# mikrokontroler.net
KiCad netlist of a schematic drawn in Altium Designer
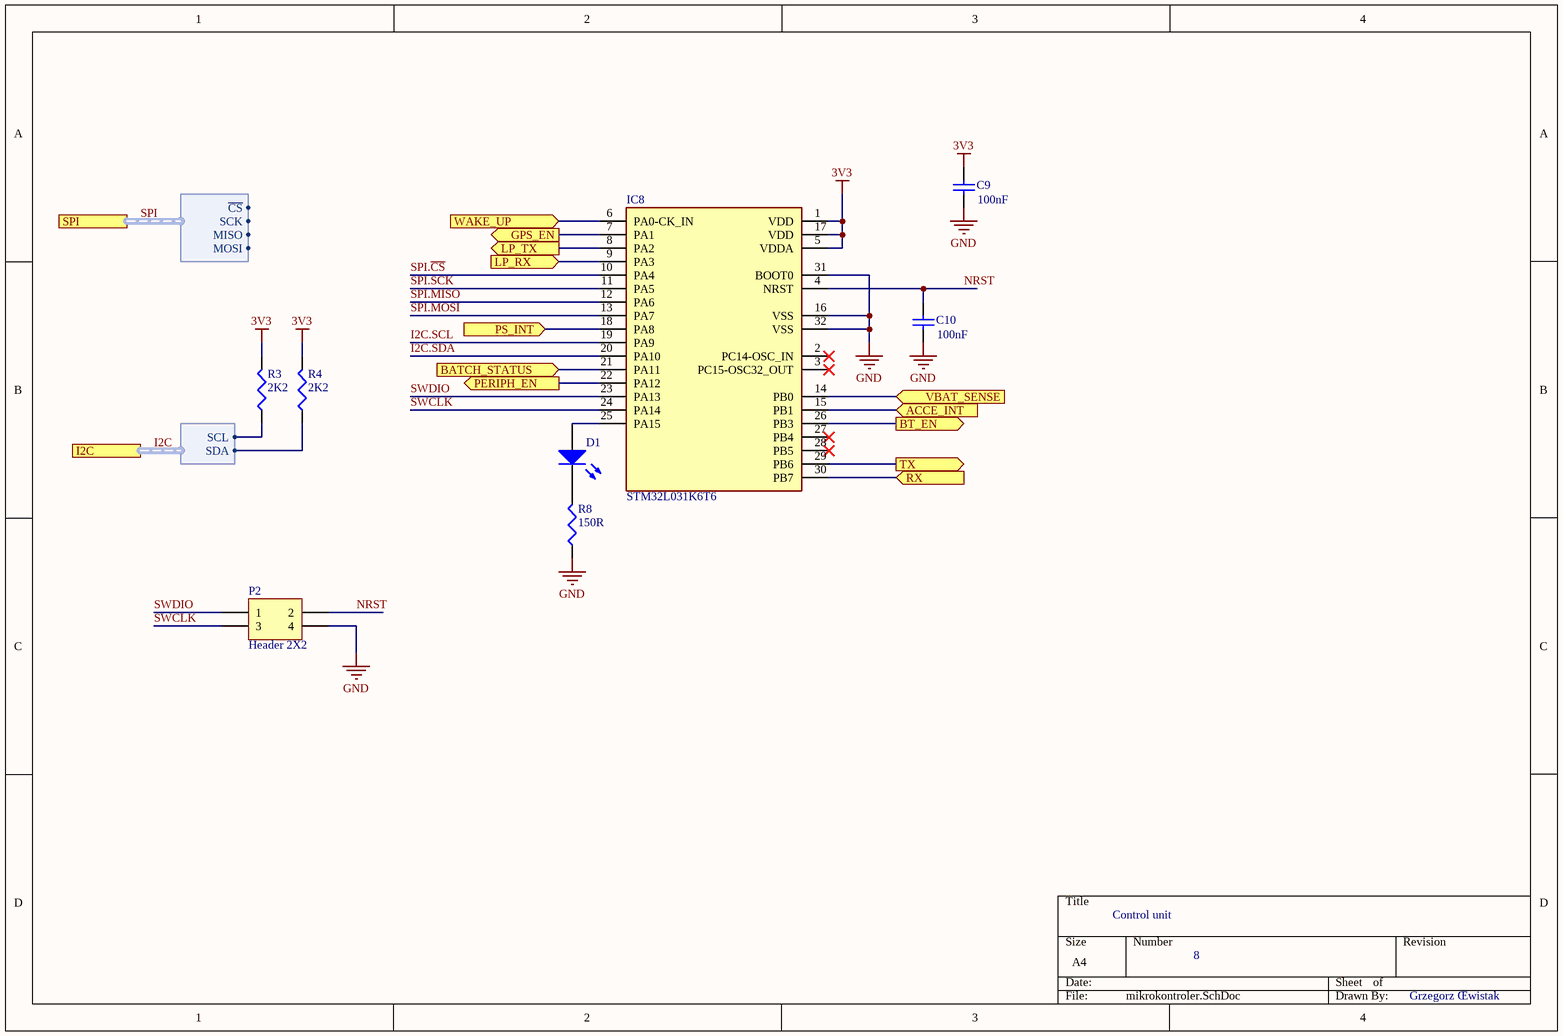
[diagram p0: mikrokontroler.SchDoc]

(export (version "E")
  (design (tool "Eeschema 10.0.6"))
  (components
    (comp (ref "C9")
      (value "100nF")
      (footprint "C0805")
      (description "Capacitor")
      (fields (field (name "Comment") "Cap") (field (name "PUBLISHER") "Altium Limited"))
      (libsource (lib "Miscellaneous Devices") (part "Cap"))
    )
    (comp (ref "C10")
      (value "100nF")
      (footprint "C0805")
      (description "Capacitor")
      (fields (field (name "Comment") "Cap") (field (name "PUBLISHER") "Altium Limited"))
      (libsource (lib "Miscellaneous Devices") (part "Cap"))
    )
    (comp (ref "D1")
      (value "LL-S192PUAC-2A")
      (footprint "LED_0603")
      (description "Typical BLUE SiC LED")
      (fields (field (name "PUBLISHER") "Altium Limited"))
      (libsource (lib "Miscellaneous Devices") (part "LED3"))
    )
    (comp (ref "IC8")
      (value "STM32L031K6T6")
      (footprint "QFP80P900X900X160-32N")
      (description "Integrated Circuit")
      (fields (field (name "MOUSER PART NUMBER") "511-STM32L031K6T6"))
      (libsource (lib "lib") (part "STM32L031K6T6"))
    )
    (comp (ref "P2")
      (value "Header 2X2")
      (footprint "2x2_header")
      (description "Header, 2-Pin, Dual row")
      (fields (field (name "PUBLISHER") "Altium Limited"))
      (libsource (lib "Miscellaneous Connectors") (part "Header 2X2"))
    )
    (comp (ref "R3")
      (value "2K2")
      (footprint "R0603")
      (description "Resistor")
      (fields (field (name "Comment") "Res3") (field (name "PUBLISHER") "Altium Limited"))
      (libsource (lib "Miscellaneous Devices") (part "Res3"))
    )
    (comp (ref "R4")
      (value "2K2")
      (footprint "R0603")
      (description "Resistor")
      (fields (field (name "Comment") "Res3") (field (name "PUBLISHER") "Altium Limited"))
      (libsource (lib "Miscellaneous Devices") (part "Res3"))
    )
    (comp (ref "R8")
      (value "150R")
      (footprint "R0603")
      (description "Resistor")
      (fields (field (name "Comment") "Res3") (field (name "PUBLISHER") "Altium Limited"))
      (libsource (lib "Miscellaneous Devices") (part "Res3"))
    )
  )
  (nets
    (net (code "3") (name "/ACCE_INT") (class "Default")
      (node (ref "IC8") (pin "15") (pinfunction "PB1_15") (pintype "passive"))
    )
    (net (code "4") (name "/BATCH_STATUS") (class "Default")
      (node (ref "IC8") (pin "21") (pinfunction "PA11_21") (pintype "passive"))
    )
    (net (code "5") (name "/BT_EN") (class "Default")
      (node (ref "IC8") (pin "26") (pinfunction "PB3_26") (pintype "passive"))
    )
    (net (code "6") (name "/GPS_EN") (class "Default")
      (node (ref "IC8") (pin "7") (pinfunction "PA1_7") (pintype "passive"))
    )
    (net (code "7") (name "/I2C.SCL") (class "Default")
      (node (ref "IC8") (pin "19") (pinfunction "PA9_19") (pintype "passive"))
    )
    (net (code "8") (name "/I2C.SDA") (class "Default")
      (node (ref "IC8") (pin "20") (pinfunction "PA10_20") (pintype "passive"))
    )
    (net (code "10") (name "/LP_RX") (class "Default")
      (node (ref "IC8") (pin "9") (pinfunction "PA3_9") (pintype "passive"))
    )
    (net (code "11") (name "/LP_TX") (class "Default")
      (node (ref "IC8") (pin "8") (pinfunction "PA2_8") (pintype "passive"))
    )
    (net (code "12") (name "/NRST") (class "Default")
      (node (ref "C10") (pin "2") (pinfunction "2_2") (pintype "passive"))
      (node (ref "IC8") (pin "4") (pinfunction "NRST_4") (pintype "passive"))
      (node (ref "P2") (pin "2") (pinfunction "2_2") (pintype "passive"))
    )
    (net (code "13") (name "/PERIPH_EN") (class "Default")
      (node (ref "IC8") (pin "22") (pinfunction "PA12_22") (pintype "passive"))
    )
    (net (code "14") (name "/PS_INT") (class "Default")
      (node (ref "IC8") (pin "18") (pinfunction "PA8_18") (pintype "passive"))
    )
    (net (code "15") (name "/RX") (class "Default")
      (node (ref "IC8") (pin "30") (pinfunction "PB7_30") (pintype "passive"))
    )
    (net (code "16") (name "/SCL") (class "Default")
      (node (ref "R3") (pin "1") (pinfunction "1_1") (pintype "passive"))
    )
    (net (code "17") (name "/SDA") (class "Default")
      (node (ref "R4") (pin "1") (pinfunction "1_1") (pintype "passive"))
    )
    (net (code "18") (name "/SPI.MISO") (class "Default")
      (node (ref "IC8") (pin "12") (pinfunction "PA6_12") (pintype "passive"))
    )
    (net (code "19") (name "/SPI.MOSI") (class "Default")
      (node (ref "IC8") (pin "13") (pinfunction "PA7_13") (pintype "passive"))
    )
    (net (code "20") (name "/SPI.SCK") (class "Default")
      (node (ref "IC8") (pin "11") (pinfunction "PA5_11") (pintype "passive"))
    )
    (net (code "21") (name "/SPI.~{CS}") (class "Default")
      (node (ref "IC8") (pin "10") (pinfunction "PA4_10") (pintype "passive"))
    )
    (net (code "23") (name "/SWCLK") (class "Default")
      (node (ref "IC8") (pin "24") (pinfunction "PA14_24") (pintype "passive"))
      (node (ref "P2") (pin "3") (pinfunction "3_3") (pintype "passive"))
    )
    (net (code "24") (name "/SWDIO") (class "Default")
      (node (ref "IC8") (pin "23") (pinfunction "PA13_23") (pintype "passive"))
      (node (ref "P2") (pin "1") (pinfunction "1_1") (pintype "passive"))
    )
    (net (code "25") (name "/TX") (class "Default")
      (node (ref "IC8") (pin "29") (pinfunction "PB6_29") (pintype "passive"))
    )
    (net (code "26") (name "/VBAT_SENSE") (class "Default")
      (node (ref "IC8") (pin "14") (pinfunction "PB0_14") (pintype "passive"))
    )
    (net (code "27") (name "/WAKE_UP") (class "Default")
      (node (ref "IC8") (pin "6") (pinfunction "PA0-CK_IN_6") (pintype "passive"))
    )
    (net (code "28") (name "3V3") (class "Default")
      (node (ref "C9") (pin "2") (pinfunction "2_2") (pintype "passive"))
      (node (ref "IC8") (pin "1") (pinfunction "VDD_1") (pintype "passive"))
      (node (ref "IC8") (pin "17") (pinfunction "VDD_17") (pintype "passive"))
      (node (ref "IC8") (pin "5") (pinfunction "VDDA_5") (pintype "passive"))
      (node (ref "R3") (pin "2") (pinfunction "2_2") (pintype "passive"))
      (node (ref "R4") (pin "2") (pinfunction "2_2") (pintype "passive"))
    )
    (net (code "29") (name "GND") (class "Default")
      (node (ref "C10") (pin "1") (pinfunction "1_1") (pintype "passive"))
      (node (ref "C9") (pin "1") (pinfunction "1_1") (pintype "passive"))
      (node (ref "IC8") (pin "16") (pinfunction "VSS_16") (pintype "passive"))
      (node (ref "IC8") (pin "31") (pinfunction "BOOT0_31") (pintype "passive"))
      (node (ref "IC8") (pin "32") (pinfunction "VSS_32") (pintype "passive"))
      (node (ref "P2") (pin "4") (pinfunction "4_4") (pintype "passive"))
      (node (ref "R8") (pin "1") (pinfunction "1_1") (pintype "passive"))
    )
    (net (code "30") (name "Net-(D1-A)") (class "Default")
      (node (ref "D1") (pin "1") (pinfunction "A_1") (pintype "passive"))
      (node (ref "IC8") (pin "25") (pinfunction "PA15_25") (pintype "passive"))
    )
    (net (code "31") (name "Net-(D1-K)") (class "Default")
      (node (ref "D1") (pin "2") (pinfunction "K_2") (pintype "passive"))
      (node (ref "R8") (pin "2") (pinfunction "2_2") (pintype "passive"))
    )
    (net (code "32") (name "unconnected-(IC8-PB4-Pad27)") (class "Default")
      (node (ref "IC8") (pin "27") (pinfunction "PB4_27") (pintype "passive+no_connect"))
    )
    (net (code "33") (name "unconnected-(IC8-PB5-Pad28)") (class "Default")
      (node (ref "IC8") (pin "28") (pinfunction "PB5_28") (pintype "passive+no_connect"))
    )
    (net (code "34") (name "unconnected-(IC8-PC14-OSC_IN-Pad2)") (class "Default")
      (node (ref "IC8") (pin "2") (pinfunction "PC14-OSC_IN_2") (pintype "passive+no_connect"))
    )
    (net (code "35") (name "unconnected-(IC8-PC15-OSC32_OUT-Pad3)") (class "Default")
      (node (ref "IC8") (pin "3") (pinfunction "PC15-OSC32_OUT_3") (pintype "passive+no_connect"))
    )
  )
)
